# uHost.net
KiCad netlist of a schematic drawn in EAGLE
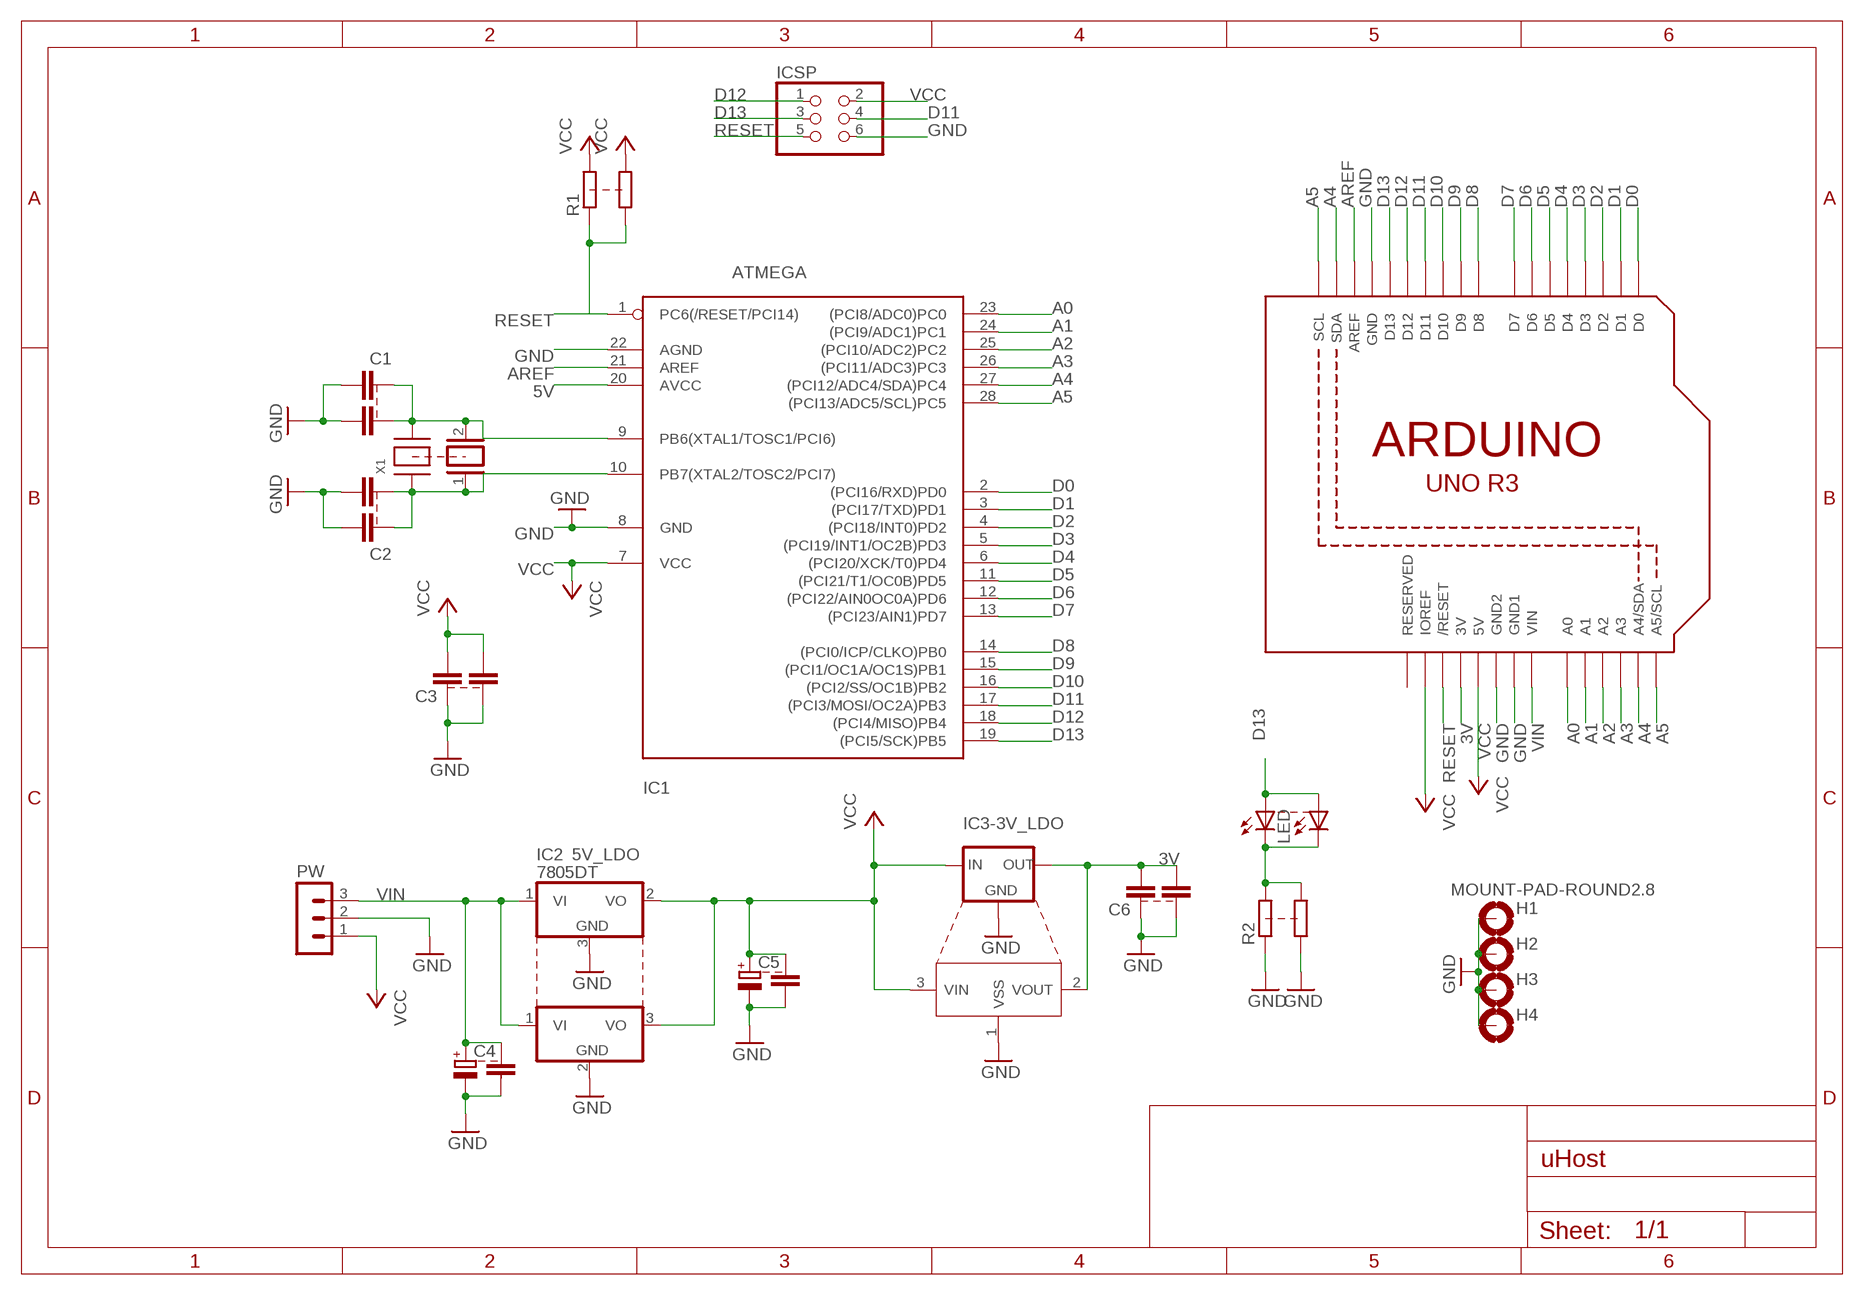
[diagram p0: schematic, sheet 1]

(export (version "E")
  (design (tool "Eeschema 10.0.6"))
  (components
    (comp (ref "C1")
      (value "C-EUC1206")
      (footprint "eagle-import:C1206")
      (libsource (lib "eagle-import") (part "C-EUC1206"))
    )
    (comp (ref "C2")
      (value "C-EUC1206")
      (footprint "eagle-import:C1206")
      (libsource (lib "eagle-import") (part "C-EUC1206"))
    )
    (comp (ref "C3")
      (value "C-EU050-025X075")
      (footprint "eagle-import:C050-025X075")
      (libsource (lib "eagle-import") (part "resistor_C-EU050-025X075"))
    )
    (comp (ref "C4")
      (value "CPOL-EUE2.5-6")
      (footprint "eagle-import:E2,5-6")
      (libsource (lib "eagle-import") (part "CPOL-EUE2.5-6"))
    )
    (comp (ref "C5")
      (value "CPOL-EUE2.5-6")
      (footprint "eagle-import:E2,5-6")
      (libsource (lib "eagle-import") (part "CPOL-EUE2.5-6"))
    )
    (comp (ref "C6")
      (value "C-EU050-025X075")
      (footprint "eagle-import:C050-025X075")
      (libsource (lib "eagle-import") (part "resistor_C-EU050-025X075"))
    )
    (comp (ref "C21")
      (value "C-EU050-025X075")
      (footprint "eagle-import:C050-025X075")
      (libsource (lib "eagle-import") (part "resistor_C-EU050-025X075"))
    )
    (comp (ref "C22")
      (value "C-EU050-025X075")
      (footprint "eagle-import:C050-025X075")
      (libsource (lib "eagle-import") (part "resistor_C-EU050-025X075"))
    )
    (comp (ref "C23")
      (value "C-EUC1206")
      (footprint "eagle-import:C1206")
      (libsource (lib "eagle-import") (part "C-EUC1206"))
    )
    (comp (ref "C24")
      (value "C-EUC1206")
      (footprint "eagle-import:C1206")
      (libsource (lib "eagle-import") (part "C-EUC1206"))
    )
    (comp (ref "C25")
      (value "C-EUC1206")
      (footprint "eagle-import:C1206")
      (libsource (lib "eagle-import") (part "C-EUC1206"))
    )
    (comp (ref "C26")
      (value "C-EUC1206")
      (footprint "eagle-import:C1206")
      (libsource (lib "eagle-import") (part "C-EUC1206"))
    )
    (comp (ref "H1")
      (value "MOUNT-PAD-ROUND2.8")
      (footprint "eagle-import:2,8-PAD")
      (libsource (lib "eagle-import") (part "MOUNT-PAD-ROUND2.8"))
    )
    (comp (ref "H2")
      (value "MOUNT-PAD-ROUND2.8")
      (footprint "eagle-import:2,8-PAD")
      (libsource (lib "eagle-import") (part "MOUNT-PAD-ROUND2.8"))
    )
    (comp (ref "H3")
      (value "MOUNT-PAD-ROUND2.8")
      (footprint "eagle-import:2,8-PAD")
      (libsource (lib "eagle-import") (part "MOUNT-PAD-ROUND2.8"))
    )
    (comp (ref "H4")
      (value "MOUNT-PAD-ROUND2.8")
      (footprint "eagle-import:2,8-PAD")
      (libsource (lib "eagle-import") (part "MOUNT-PAD-ROUND2.8"))
    )
    (comp (ref "IC1")
      (value "ATMEGA")
      (footprint "eagle-import:DIL28-3")
      (libsource (lib "eagle-import") (part "ATMEGA168P-20"))
    )
    (comp (ref "IC2")
      (value "7805DT")
      (footprint "eagle-import:TO252")
      (libsource (lib "eagle-import") (part "78DT05"))
    )
    (comp (ref "IC3-3V_LDO")
      (value "78LXX")
      (footprint "eagle-import:78LXX")
      (libsource (lib "eagle-import") (part "78LXX"))
    )
    (comp (ref "IC23")
      (value "5V_LDO")
      (footprint "eagle-import:TO220H")
      (libsource (lib "eagle-import") (part "78T05"))
    )
    (comp (ref "ICSP")
      (value "PINHD-2X3")
      (footprint "eagle-import:2X03")
      (libsource (lib "eagle-import") (part "PINHD-2X3"))
    )
    (comp (ref "LED")
      (value "LED3MM")
      (footprint "eagle-import:LED3MM")
      (libsource (lib "eagle-import") (part "LED3MM"))
    )
    (comp (ref "LED1")
      (value "LEDCHIPLED_1206")
      (footprint "eagle-import:CHIPLED_1206")
      (libsource (lib "eagle-import") (part "led_LEDCHIPLED_1206"))
    )
    (comp (ref "PW")
      (value "MA03-1")
      (footprint "eagle-import:MA03-1")
      (libsource (lib "eagle-import") (part "MA03-1"))
    )
    (comp (ref "Q2")
      (value "XTAL/S")
      (footprint "eagle-import:QS")
      (libsource (lib "eagle-import") (part "XTAL/S"))
    )
    (comp (ref "R1")
      (value "R-EU_0207/7")
      (footprint "eagle-import:0207_7")
      (libsource (lib "eagle-import") (part "R-EU_0207/7"))
    )
    (comp (ref "R2")
      (value "R-EU_0207/7")
      (footprint "eagle-import:0207_7")
      (libsource (lib "eagle-import") (part "R-EU_0207/7"))
    )
    (comp (ref "R21")
      (value "R-EU_R1206")
      (footprint "eagle-import:R1206")
      (libsource (lib "eagle-import") (part "R-EU_R1206"))
    )
    (comp (ref "R22")
      (value "R-EU_R1206")
      (footprint "eagle-import:R1206")
      (libsource (lib "eagle-import") (part "R-EU_R1206"))
    )
    (comp (ref "U1")
      (value "ARDUINOR3-BPLACE")
      (footprint "eagle-import:ARDUINOR3-BPLACE")
      (libsource (lib "eagle-import") (part "ARDUINOR3-BPLACE"))
    )
    (comp (ref "U2")
      (value "XC6206-3.3-1300260P1")
      (footprint "eagle-import:SOT23")
      (libsource (lib "eagle-import") (part "XC6206-3.3-1300260P1"))
    )
    (comp (ref "X1")
      (value "XTALNX5032")
      (footprint "eagle-import:NX5032")
      (libsource (lib "eagle-import") (part "XTALNX5032"))
    )
  )
  (nets
    (net (code "1") (name "/3V") (class "Default")
      (node (ref "C26") (pin "2") (pinfunction "2_2") (pintype "passive"))
      (node (ref "C6") (pin "2") (pinfunction "2_2") (pintype "passive"))
      (node (ref "IC3-3V_LDO") (pin "OUT") (pinfunction "OUT_OUT") (pintype "passive"))
      (node (ref "U1") (pin "3V") (pinfunction "3V_3V") (pintype "power_in"))
      (node (ref "U2") (pin "2") (pinfunction "VOUT_2") (pintype "output"))
    )
    (net (code "2") (name "/5V") (class "Default")
      (node (ref "IC1") (pin "20") (pinfunction "AVCC_20") (pintype "bidirectional"))
    )
    (net (code "3") (name "/A0") (class "Default")
      (node (ref "IC1") (pin "23") (pinfunction "(PCI8/ADC0)PC0_23") (pintype "bidirectional"))
      (node (ref "U1") (pin "A0") (pinfunction "A0_A0") (pintype "bidirectional"))
    )
    (net (code "4") (name "/A1") (class "Default")
      (node (ref "IC1") (pin "24") (pinfunction "(PCI9/ADC1)PC1_24") (pintype "bidirectional"))
      (node (ref "U1") (pin "A1") (pinfunction "A1_A1") (pintype "bidirectional"))
    )
    (net (code "5") (name "/A2") (class "Default")
      (node (ref "IC1") (pin "25") (pinfunction "(PCI10/ADC2)PC2_25") (pintype "bidirectional"))
      (node (ref "U1") (pin "A2") (pinfunction "A2_A2") (pintype "bidirectional"))
    )
    (net (code "6") (name "/A3") (class "Default")
      (node (ref "IC1") (pin "26") (pinfunction "(PCI11/ADC3)PC3_26") (pintype "bidirectional"))
      (node (ref "U1") (pin "A3") (pinfunction "A3_A3") (pintype "bidirectional"))
    )
    (net (code "7") (name "/A4") (class "Default")
      (node (ref "IC1") (pin "27") (pinfunction "(PCI12/ADC4/SDA)PC4_27") (pintype "bidirectional"))
      (node (ref "U1") (pin "A4") (pinfunction "A4/SDA_A4") (pintype "bidirectional"))
      (node (ref "U1") (pin "SDA") (pinfunction "SDA_SDA") (pintype "bidirectional"))
    )
    (net (code "8") (name "/A5") (class "Default")
      (node (ref "IC1") (pin "28") (pinfunction "(PCI13/ADC5/SCL)PC5_28") (pintype "bidirectional"))
      (node (ref "U1") (pin "A5") (pinfunction "A5/SCL_A5") (pintype "bidirectional"))
      (node (ref "U1") (pin "SCL") (pinfunction "SCL_SCL") (pintype "bidirectional"))
    )
    (net (code "9") (name "/AREF") (class "Default")
      (node (ref "IC1") (pin "21") (pinfunction "AREF_21") (pintype "bidirectional"))
      (node (ref "U1") (pin "AREF") (pinfunction "AREF_AREF") (pintype "bidirectional"))
    )
    (net (code "10") (name "/D0") (class "Default")
      (node (ref "IC1") (pin "2") (pinfunction "(PCI16/RXD)PD0_2") (pintype "bidirectional"))
      (node (ref "U1") (pin "D0") (pinfunction "D0_D0") (pintype "bidirectional"))
    )
    (net (code "11") (name "/D1") (class "Default")
      (node (ref "IC1") (pin "3") (pinfunction "(PCI17/TXD)PD1_3") (pintype "bidirectional"))
      (node (ref "U1") (pin "D1") (pinfunction "D1_D1") (pintype "bidirectional"))
    )
    (net (code "12") (name "/D2") (class "Default")
      (node (ref "IC1") (pin "4") (pinfunction "(PCI18/INT0)PD2_4") (pintype "bidirectional"))
      (node (ref "U1") (pin "D2") (pinfunction "D2_D2") (pintype "bidirectional"))
    )
    (net (code "13") (name "/D3") (class "Default")
      (node (ref "IC1") (pin "5") (pinfunction "(PCI19/INT1/OC2B)PD3_5") (pintype "bidirectional"))
      (node (ref "U1") (pin "D3") (pinfunction "D3_D3") (pintype "bidirectional"))
    )
    (net (code "14") (name "/D4") (class "Default")
      (node (ref "IC1") (pin "6") (pinfunction "(PCI20/XCK/T0)PD4_6") (pintype "bidirectional"))
      (node (ref "U1") (pin "D4") (pinfunction "D4_D4") (pintype "bidirectional"))
    )
    (net (code "15") (name "/D5") (class "Default")
      (node (ref "IC1") (pin "11") (pinfunction "(PCI21/T1/OC0B)PD5_11") (pintype "bidirectional"))
      (node (ref "U1") (pin "D5") (pinfunction "D5_D5") (pintype "bidirectional"))
    )
    (net (code "16") (name "/D6") (class "Default")
      (node (ref "IC1") (pin "12") (pinfunction "(PCI22/AIN0OC0A)PD6_12") (pintype "bidirectional"))
      (node (ref "U1") (pin "D6") (pinfunction "D6_D6") (pintype "bidirectional"))
    )
    (net (code "17") (name "/D7") (class "Default")
      (node (ref "IC1") (pin "13") (pinfunction "(PCI23/AIN1)PD7_13") (pintype "bidirectional"))
      (node (ref "U1") (pin "D7") (pinfunction "D7_D7") (pintype "bidirectional"))
    )
    (net (code "18") (name "/D8") (class "Default")
      (node (ref "IC1") (pin "14") (pinfunction "(PCI0/ICP/CLKO)PB0_14") (pintype "bidirectional"))
      (node (ref "U1") (pin "D8") (pinfunction "D8_D8") (pintype "bidirectional"))
    )
    (net (code "19") (name "/D9") (class "Default")
      (node (ref "IC1") (pin "15") (pinfunction "(PCI1/OC1A/OC1S)PB1_15") (pintype "bidirectional"))
      (node (ref "U1") (pin "D9") (pinfunction "D9_D9") (pintype "bidirectional"))
    )
    (net (code "20") (name "/D10") (class "Default")
      (node (ref "IC1") (pin "16") (pinfunction "(PCI2/SS/OC1B)PB2_16") (pintype "bidirectional"))
      (node (ref "U1") (pin "D10") (pinfunction "D10_D10") (pintype "bidirectional"))
    )
    (net (code "21") (name "/D11") (class "Default")
      (node (ref "IC1") (pin "17") (pinfunction "(PCI3/MOSI/OC2A)PB3_17") (pintype "bidirectional"))
      (node (ref "ICSP") (pin "4") (pinfunction "4_4") (pintype "passive"))
      (node (ref "U1") (pin "D11") (pinfunction "D11_D11") (pintype "bidirectional"))
    )
    (net (code "22") (name "/D12") (class "Default")
      (node (ref "IC1") (pin "18") (pinfunction "(PCI4/MISO)PB4_18") (pintype "bidirectional"))
      (node (ref "ICSP") (pin "1") (pinfunction "1_1") (pintype "passive"))
      (node (ref "U1") (pin "D12") (pinfunction "D12_D12") (pintype "bidirectional"))
    )
    (net (code "23") (name "/D13") (class "Default")
      (node (ref "IC1") (pin "19") (pinfunction "(PCI5/SCK)PB5_19") (pintype "bidirectional"))
      (node (ref "ICSP") (pin "3") (pinfunction "3_3") (pintype "passive"))
      (node (ref "LED") (pin "A") (pinfunction "A_A") (pintype "passive"))
      (node (ref "LED1") (pin "A") (pinfunction "A_A") (pintype "passive"))
      (node (ref "U1") (pin "D13") (pinfunction "D13_D13") (pintype "bidirectional"))
    )
    (net (code "24") (name "/RESET") (class "Default")
      (node (ref "IC1") (pin "1") (pinfunction "PC6(/RESET/PCI14)_1") (pintype "bidirectional"))
      (node (ref "ICSP") (pin "5") (pinfunction "5_5") (pintype "passive"))
      (node (ref "R1") (pin "1") (pinfunction "1_1") (pintype "passive"))
      (node (ref "R21") (pin "1") (pinfunction "1_1") (pintype "passive"))
      (node (ref "U1") (pin "RESET") (pinfunction "/RESET_RESET") (pintype "bidirectional"))
    )
    (net (code "25") (name "/VIN") (class "Default")
      (node (ref "C24") (pin "1") (pinfunction "1_1") (pintype "passive"))
      (node (ref "C4") (pin "+") (pinfunction "+_+") (pintype "passive"))
      (node (ref "IC2") (pin "1") (pinfunction "VI_1") (pintype "input"))
      (node (ref "IC23") (pin "1") (pinfunction "VI_1") (pintype "input"))
      (node (ref "PW") (pin "3") (pinfunction "3_3") (pintype "passive"))
      (node (ref "U1") (pin "VIN") (pinfunction "VIN_VIN") (pintype "power_in"))
    )
    (net (code "26") (name "GND") (class "Default")
      (node (ref "C1") (pin "2") (pinfunction "2_2") (pintype "passive"))
      (node (ref "C2") (pin "2") (pinfunction "2_2") (pintype "passive"))
      (node (ref "C21") (pin "2") (pinfunction "2_2") (pintype "passive"))
      (node (ref "C22") (pin "2") (pinfunction "2_2") (pintype "passive"))
      (node (ref "C23") (pin "1") (pinfunction "1_1") (pintype "passive"))
      (node (ref "C24") (pin "2") (pinfunction "2_2") (pintype "passive"))
      (node (ref "C25") (pin "2") (pinfunction "2_2") (pintype "passive"))
      (node (ref "C26") (pin "1") (pinfunction "1_1") (pintype "passive"))
      (node (ref "C3") (pin "1") (pinfunction "1_1") (pintype "passive"))
      (node (ref "C4") (pin "-") (pinfunction "-_-") (pintype "passive"))
      (node (ref "C5") (pin "-") (pinfunction "-_-") (pintype "passive"))
      (node (ref "C6") (pin "1") (pinfunction "1_1") (pintype "passive"))
      (node (ref "H1") (pin "B2,8") (pinfunction "MOUNT_B2,8") (pintype "passive"))
      (node (ref "H2") (pin "B2,8") (pinfunction "MOUNT_B2,8") (pintype "passive"))
      (node (ref "H3") (pin "B2,8") (pinfunction "MOUNT_B2,8") (pintype "passive"))
      (node (ref "H4") (pin "B2,8") (pinfunction "MOUNT_B2,8") (pintype "passive"))
      (node (ref "IC1") (pin "22") (pinfunction "AGND_22") (pintype "bidirectional"))
      (node (ref "IC1") (pin "8") (pinfunction "GND_8") (pintype "bidirectional"))
      (node (ref "IC2") (pin "3") (pinfunction "GND_3") (pintype "passive"))
      (node (ref "IC23") (pin "2") (pinfunction "GND_2") (pintype "passive"))
      (node (ref "IC3-3V_LDO") (pin "GND") (pinfunction "GND_GND") (pintype "input"))
      (node (ref "ICSP") (pin "6") (pinfunction "6_6") (pintype "passive"))
      (node (ref "PW") (pin "2") (pinfunction "2_2") (pintype "passive"))
      (node (ref "R2") (pin "1") (pinfunction "1_1") (pintype "passive"))
      (node (ref "R22") (pin "1") (pinfunction "1_1") (pintype "passive"))
      (node (ref "U1") (pin "GND") (pinfunction "GND_GND") (pintype "power_in"))
      (node (ref "U1") (pin "GND1") (pinfunction "GND1_GND1") (pintype "power_in"))
      (node (ref "U1") (pin "GND2") (pinfunction "GND2_GND2") (pintype "power_in"))
      (node (ref "U2") (pin "1") (pinfunction "VSS_1") (pintype "power_in"))
    )
    (net (code "27") (name "Net-(IC1-PB6(XTAL1{slash}TOSC1{slash}PCI6))") (class "Default")
      (node (ref "C1") (pin "1") (pinfunction "1_1") (pintype "passive"))
      (node (ref "C21") (pin "1") (pinfunction "1_1") (pintype "passive"))
      (node (ref "IC1") (pin "9") (pinfunction "PB6(XTAL1/TOSC1/PCI6)_9") (pintype "bidirectional"))
      (node (ref "Q2") (pin "2") (pinfunction "2_2") (pintype "passive"))
      (node (ref "X1") (pin "P$2") (pinfunction "P$2_P$2") (pintype "bidirectional"))
    )
    (net (code "28") (name "Net-(IC1-PB7(XTAL2{slash}TOSC2{slash}PCI7))") (class "Default")
      (node (ref "C2") (pin "1") (pinfunction "1_1") (pintype "passive"))
      (node (ref "C22") (pin "1") (pinfunction "1_1") (pintype "passive"))
      (node (ref "IC1") (pin "10") (pinfunction "PB7(XTAL2/TOSC2/PCI7)_10") (pintype "bidirectional"))
      (node (ref "Q2") (pin "1") (pinfunction "1_1") (pintype "passive"))
      (node (ref "X1") (pin "P$1") (pinfunction "P$1_P$1") (pintype "bidirectional"))
    )
    (net (code "29") (name "Net-(LED-C)") (class "Default")
      (node (ref "LED") (pin "K") (pinfunction "C_K") (pintype "passive"))
      (node (ref "LED1") (pin "C") (pinfunction "C_C") (pintype "passive"))
      (node (ref "R2") (pin "2") (pinfunction "2_2") (pintype "passive"))
      (node (ref "R22") (pin "2") (pinfunction "2_2") (pintype "passive"))
    )
    (net (code "30") (name "VCC") (class "Default")
      (node (ref "C23") (pin "2") (pinfunction "2_2") (pintype "passive"))
      (node (ref "C25") (pin "1") (pinfunction "1_1") (pintype "passive"))
      (node (ref "C3") (pin "2") (pinfunction "2_2") (pintype "passive"))
      (node (ref "C5") (pin "+") (pinfunction "+_+") (pintype "passive"))
      (node (ref "IC1") (pin "7") (pinfunction "VCC_7") (pintype "bidirectional"))
      (node (ref "IC2") (pin "2") (pinfunction "VO_2") (pintype "passive"))
      (node (ref "IC23") (pin "3") (pinfunction "VO_3") (pintype "passive"))
      (node (ref "IC3-3V_LDO") (pin "IN") (pinfunction "IN_IN") (pintype "input"))
      (node (ref "ICSP") (pin "2") (pinfunction "2_2") (pintype "passive"))
      (node (ref "PW") (pin "1") (pinfunction "1_1") (pintype "passive"))
      (node (ref "R1") (pin "2") (pinfunction "2_2") (pintype "passive"))
      (node (ref "R21") (pin "2") (pinfunction "2_2") (pintype "passive"))
      (node (ref "U1") (pin "5V") (pinfunction "5V_5V") (pintype "power_in"))
      (node (ref "U1") (pin "IOREF") (pinfunction "IOREF_IOREF") (pintype "output"))
      (node (ref "U2") (pin "3") (pinfunction "VIN_3") (pintype "input"))
    )
    (net (code "31") (name "unconnected-(U1-PadRESERVED)") (class "Default")
      (node (ref "U1") (pin "RESERVED") (pinfunction "RESERVED_RESERVED") (pintype "no_connect"))
    )
  )
)
